# Regulation_Charging.net
KiCad netlist of a schematic drawn in Altium Designer
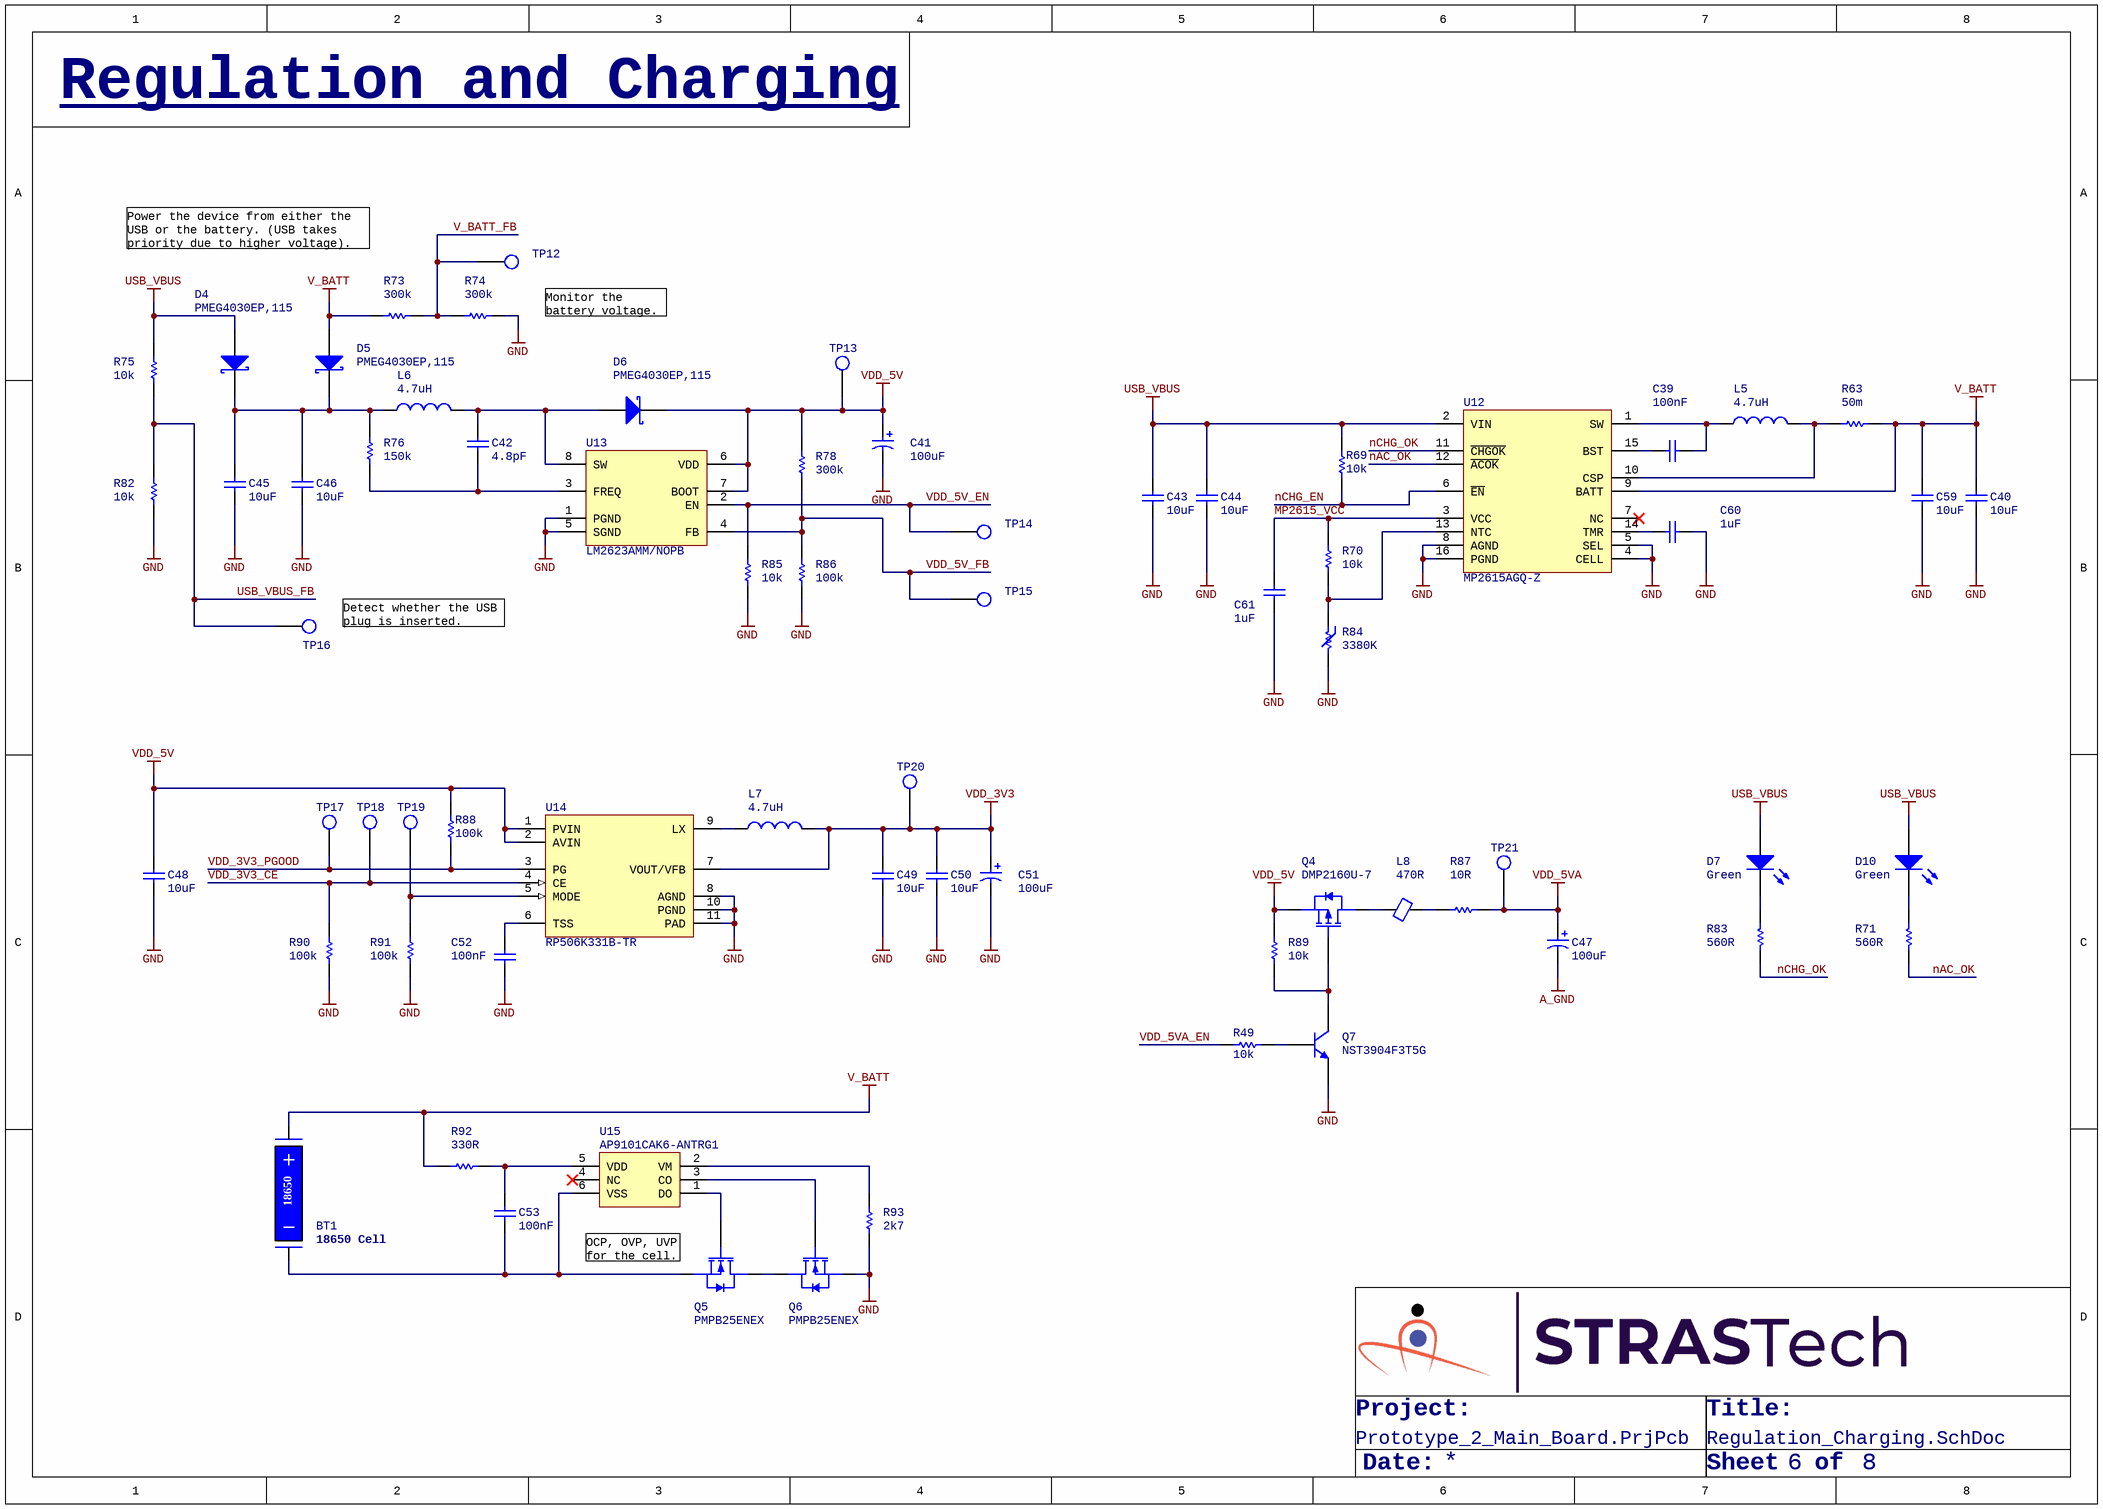
[diagram p0: Regulation_Charging.SchDoc]

(export (version "E")
  (design (tool "Eeschema 10.0.6"))
  (components
    (comp (ref "BT1")
      (value "Holder,Cell,18650,SMD")
      (footprint "HOLDER,CELL,18650,SMD")
      (description "Battery Holder (Open) 18650 1 Cell SMD (SMT) Tab")
      (fields
        (field (name "MANUFACTURER") "Keystone Electronics")
        (field (name "MANUFACTURER PART NUMBER") "1042")
        (field (name "CREATEDBY") "Judd Foster")
      )
      (libsource (lib "symbols") (part "Holder,Cell,18650,SMD"))
    )
    (comp (ref "C39")
      (value "100nF")
      (footprint "Cap,SMD,0402")
      (description "0.1µF ±10% 25V Ceramic Capacitor X7R 0402 (1005 Metric)")
      (fields
        (field (name "VENDOR PART NUMBER") "490-14603-1-ND")
        (field (name "MANUFACTURER") "Murata Electronics")
        (field (name "CREATEDBY") "Judd Foster")
      )
      (libsource (lib "symbols") (part "CAP,Cer,100nF,25VDC,X7R,0402"))
    )
    (comp (ref "C40")
      (value "10uF")
      (footprint "Cap,SMD,0402")
      (description "10 µF ±20% 10V Ceramic Capacitor X5R 0402 (1005 Metric)")
      (fields
        (field (name "VENDOR PART NUMBER") "1276-1450-1-ND")
        (field (name "MANUFACTURER") "Samsung Electro-Mechanics")
        (field (name "CREATEDBY") "Judd Foster")
      )
      (libsource (lib "symbols") (part "CAP,Cer,10uF,10VDC,X5R,0402"))
    )
    (comp (ref "C41")
      (value "100uF")
      (footprint "Cap,Alum,SMD,D5,H5.8")
      (description "CAP ALUM 100UF 20% 10V SMD")
      (fields
        (field (name "VENDOR PART NUMBER") "PCE3867CT-ND")
        (field (name "MANUFACTURER") "Panasonic")
        (field (name "CREATEDBY") "Judd Foster")
      )
      (libsource (lib "symbols") (part "CAP,Alum,100uF,10VDC,SMD"))
    )
    (comp (ref "C42")
      (value "4.8pF")
      (footprint "Cap,SMD,0402")
      (description "4.8 pF ±0.25pF 50V Ceramic Capacitor C0G, NP0 0402 (1005 Metric)")
      (fields
        (field (name "VENDOR PART NUMBER") "490-17481-1-ND")
        (field (name "MANUFACTURER") "Murata Electronics")
        (field (name "CREATEDBY") "Judd Foster")
      )
      (libsource (lib "symbols") (part "CAP,Cer,4.8pF,50VDC,C0G/NP0,0402"))
    )
    (comp (ref "C43")
      (value "10uF")
      (footprint "Cap,SMD,0402")
      (description "10 µF ±20% 10V Ceramic Capacitor X5R 0402 (1005 Metric)")
      (fields
        (field (name "VENDOR PART NUMBER") "1276-1450-1-ND")
        (field (name "MANUFACTURER") "Samsung Electro-Mechanics")
        (field (name "CREATEDBY") "Judd Foster")
      )
      (libsource (lib "symbols") (part "CAP,Cer,10uF,10VDC,X5R,0402"))
    )
    (comp (ref "C44")
      (value "10uF")
      (footprint "Cap,SMD,0402")
      (description "10 µF ±20% 10V Ceramic Capacitor X5R 0402 (1005 Metric)")
      (fields
        (field (name "VENDOR PART NUMBER") "1276-1450-1-ND")
        (field (name "MANUFACTURER") "Samsung Electro-Mechanics")
        (field (name "CREATEDBY") "Judd Foster")
      )
      (libsource (lib "symbols") (part "CAP,Cer,10uF,10VDC,X5R,0402"))
    )
    (comp (ref "C45")
      (value "10uF")
      (footprint "Cap,SMD,0402")
      (description "10 µF ±20% 10V Ceramic Capacitor X5R 0402 (1005 Metric)")
      (fields
        (field (name "VENDOR PART NUMBER") "1276-1450-1-ND")
        (field (name "MANUFACTURER") "Samsung Electro-Mechanics")
        (field (name "CREATEDBY") "Judd Foster")
      )
      (libsource (lib "symbols") (part "CAP,Cer,10uF,10VDC,X5R,0402"))
    )
    (comp (ref "C46")
      (value "10uF")
      (footprint "Cap,SMD,0402")
      (description "10 µF ±20% 10V Ceramic Capacitor X5R 0402 (1005 Metric)")
      (fields
        (field (name "VENDOR PART NUMBER") "1276-1450-1-ND")
        (field (name "MANUFACTURER") "Samsung Electro-Mechanics")
        (field (name "CREATEDBY") "Judd Foster")
      )
      (libsource (lib "symbols") (part "CAP,Cer,10uF,10VDC,X5R,0402"))
    )
    (comp (ref "C47")
      (value "100uF")
      (footprint "Cap,Alum,SMD,D5,H5.8")
      (description "CAP ALUM 100UF 20% 10V SMD")
      (fields
        (field (name "VENDOR PART NUMBER") "PCE3867CT-ND")
        (field (name "MANUFACTURER") "Panasonic")
        (field (name "CREATEDBY") "Judd Foster")
      )
      (libsource (lib "symbols") (part "CAP,Alum,100uF,10VDC,SMD"))
    )
    (comp (ref "C48")
      (value "10uF")
      (footprint "Cap,SMD,0402")
      (description "10 µF ±20% 10V Ceramic Capacitor X5R 0402 (1005 Metric)")
      (fields
        (field (name "VENDOR PART NUMBER") "1276-1450-1-ND")
        (field (name "MANUFACTURER") "Samsung Electro-Mechanics")
        (field (name "CREATEDBY") "Judd Foster")
      )
      (libsource (lib "symbols") (part "CAP,Cer,10uF,10VDC,X5R,0402"))
    )
    (comp (ref "C49")
      (value "10uF")
      (footprint "Cap,SMD,0402")
      (description "10 µF ±20% 10V Ceramic Capacitor X5R 0402 (1005 Metric)")
      (fields
        (field (name "VENDOR PART NUMBER") "1276-1450-1-ND")
        (field (name "MANUFACTURER") "Samsung Electro-Mechanics")
        (field (name "CREATEDBY") "Judd Foster")
      )
      (libsource (lib "symbols") (part "CAP,Cer,10uF,10VDC,X5R,0402"))
    )
    (comp (ref "C50")
      (value "10uF")
      (footprint "Cap,SMD,0402")
      (description "10 µF ±20% 10V Ceramic Capacitor X5R 0402 (1005 Metric)")
      (fields
        (field (name "VENDOR PART NUMBER") "1276-1450-1-ND")
        (field (name "MANUFACTURER") "Samsung Electro-Mechanics")
        (field (name "CREATEDBY") "Judd Foster")
      )
      (libsource (lib "symbols") (part "CAP,Cer,10uF,10VDC,X5R,0402"))
    )
    (comp (ref "C51")
      (value "100uF")
      (footprint "Cap,Alum,SMD,D5,H5.8")
      (description "CAP ALUM 100UF 20% 10V SMD")
      (fields
        (field (name "VENDOR PART NUMBER") "PCE3867CT-ND")
        (field (name "MANUFACTURER") "Panasonic")
        (field (name "CREATEDBY") "Judd Foster")
      )
      (libsource (lib "symbols") (part "CAP,Alum,100uF,10VDC,SMD"))
    )
    (comp (ref "C52")
      (value "100nF")
      (footprint "Cap,SMD,0402")
      (description "0.1µF ±10% 25V Ceramic Capacitor X7R 0402 (1005 Metric)")
      (fields
        (field (name "VENDOR PART NUMBER") "490-14603-1-ND")
        (field (name "MANUFACTURER") "Murata Electronics")
        (field (name "CREATEDBY") "Judd Foster")
      )
      (libsource (lib "symbols") (part "CAP,Cer,100nF,25VDC,X7R,0402"))
    )
    (comp (ref "C53")
      (value "100nF")
      (footprint "Cap,SMD,0402")
      (description "0.1µF ±10% 25V Ceramic Capacitor X7R 0402 (1005 Metric)")
      (fields
        (field (name "VENDOR PART NUMBER") "490-14603-1-ND")
        (field (name "MANUFACTURER") "Murata Electronics")
        (field (name "CREATEDBY") "Judd Foster")
      )
      (libsource (lib "symbols") (part "CAP,Cer,100nF,25VDC,X7R,0402"))
    )
    (comp (ref "C59")
      (value "10uF")
      (footprint "Cap,SMD,0402")
      (description "10 µF ±20% 10V Ceramic Capacitor X5R 0402 (1005 Metric)")
      (fields
        (field (name "VENDOR PART NUMBER") "1276-1450-1-ND")
        (field (name "MANUFACTURER") "Samsung Electro-Mechanics")
        (field (name "CREATEDBY") "Judd Foster")
      )
      (libsource (lib "symbols") (part "CAP,Cer,10uF,10VDC,X5R,0402"))
    )
    (comp (ref "C60")
      (value "1uF")
      (footprint "Cap,SMD,0402")
      (description "1 µF ±10% 35V Ceramic Capacitor X5R 0402 (1005 Metric)")
      (fields
        (field (name "VENDOR PART NUMBER") "445-9073-1-ND")
        (field (name "MANUFACTURER") "TDK Corporation")
        (field (name "CREATEDBY") "Judd Foster")
      )
      (libsource (lib "symbols") (part "CAP,Cer,1uF,35VDC,X5R,0402"))
    )
    (comp (ref "C61")
      (value "1uF")
      (footprint "Cap,SMD,0402")
      (description "1 µF ±10% 35V Ceramic Capacitor X5R 0402 (1005 Metric)")
      (fields
        (field (name "VENDOR PART NUMBER") "445-9073-1-ND")
        (field (name "MANUFACTURER") "TDK Corporation")
        (field (name "CREATEDBY") "Judd Foster")
      )
      (libsource (lib "symbols") (part "CAP,Cer,1uF,35VDC,X5R,0402"))
    )
    (comp (ref "D4")
      (value "PMEG4030EP,115")
      (footprint "SOD128")
      (description "Diode Schottky 40V 3A Surface Mount CFP5")
      (fields
        (field (name "MANUFACTURER") "Nexperia USA Inc.")
        (field (name "VENDOR PART NUMBER") "1727-5841-1-ND")
        (field (name "CREATEDBY") "Judd Foster")
      )
      (libsource (lib "symbols") (part "DIODE,Schottky,40V,3A,SMD"))
    )
    (comp (ref "D5")
      (value "PMEG4030EP,115")
      (footprint "SOD128")
      (description "Diode Schottky 40V 3A Surface Mount CFP5")
      (fields
        (field (name "MANUFACTURER") "Nexperia USA Inc.")
        (field (name "VENDOR PART NUMBER") "1727-5841-1-ND")
        (field (name "CREATEDBY") "Judd Foster")
      )
      (libsource (lib "symbols") (part "DIODE,Schottky,40V,3A,SMD"))
    )
    (comp (ref "D6")
      (value "PMEG4030EP,115")
      (footprint "SOD128")
      (description "Diode Schottky 40V 3A Surface Mount CFP5")
      (fields
        (field (name "MANUFACTURER") "Nexperia USA Inc.")
        (field (name "VENDOR PART NUMBER") "1727-5841-1-ND")
        (field (name "CREATEDBY") "Judd Foster")
      )
      (libsource (lib "symbols") (part "DIODE,Schottky,40V,3A,SMD"))
    )
    (comp (ref "D7")
      (value "Green")
      (footprint "LED,0603")
      (description "Green 530nm LED Indication - Discrete 3V 0603 (1608 Metric)")
      (fields
        (field (name "MANUFACTURER") "Stanley Electric Co")
        (field (name "MANUFACTURER PART NUMBER") "THG1111C-0005-TR")
        (field (name "CREATEDBY") "Judd Foster")
      )
      (libsource (lib "symbols") (part "LED,Green,SMD,0603"))
    )
    (comp (ref "D10")
      (value "Green")
      (footprint "LED,0603")
      (description "Green 530nm LED Indication - Discrete 3V 0603 (1608 Metric)")
      (fields
        (field (name "MANUFACTURER") "Stanley Electric Co")
        (field (name "MANUFACTURER PART NUMBER") "THG1111C-0005-TR")
        (field (name "CREATEDBY") "Judd Foster")
      )
      (libsource (lib "symbols") (part "LED,Green,SMD,0603"))
    )
    (comp (ref "L5")
      (value "4.7uH")
      (footprint "IND,WIREWOUND,4.9x4.9,SMD")
      (description "4.7µH Shielded Wirewound Inductor 2.6A 45.5mOhm Max Nonstandard")
      (fields
        (field (name "VENDOR PART NUMBER") "587-3605-1-ND")
        (field (name "MANUFACTURER") "Taiyo Yuden")
        (field (name "CREATEDBY") "Judd Foster")
      )
      (libsource (lib "symbols") (part "IND,4.7uH,2.6A,Wirewound,SMD"))
    )
    (comp (ref "L6")
      (value "4.7uH")
      (footprint "IND,WIREWOUND,4.9x4.9,SMD")
      (description "4.7µH Shielded Wirewound Inductor 2.6A 45.5mOhm Max Nonstandard")
      (fields
        (field (name "VENDOR PART NUMBER") "587-3605-1-ND")
        (field (name "MANUFACTURER") "Taiyo Yuden")
        (field (name "CREATEDBY") "Judd Foster")
      )
      (libsource (lib "symbols") (part "IND,4.7uH,2.6A,Wirewound,SMD"))
    )
    (comp (ref "L7")
      (value "4.7uH")
      (footprint "IND,WIREWOUND,4.9x4.9,SMD")
      (description "4.7µH Shielded Wirewound Inductor 2.6A 45.5mOhm Max Nonstandard")
      (fields
        (field (name "VENDOR PART NUMBER") "587-3605-1-ND")
        (field (name "MANUFACTURER") "Taiyo Yuden")
        (field (name "CREATEDBY") "Judd Foster")
      )
      (libsource (lib "symbols") (part "IND,4.7uH,2.6A,Wirewound,SMD"))
    )
    (comp (ref "L8")
      (value "470R")
      (footprint "IND,0402")
      (description "470 Ohms @ 100 MHz 1 Power Line Ferrite Bead 0402 (1005 Metric) 1A 200mOhm")
      (fields
        (field (name "VENDOR PART NUMBER") "490-10662-1-ND")
        (field (name "MANUFACTURER") "Murata Electronics")
        (field (name "CREATEDBY") "Judd Foster")
      )
      (libsource (lib "symbols") (part "Ferrite,470R@100MHz,0402"))
    )
    (comp (ref "Q4")
      (value "DMP2160U-7")
      (footprint "SOT23-3")
      (description "P-Channel 20 V 3.2A (Ta) 1.4W (Ta) Surface Mount SOT-23-3")
      (fields
        (field (name "MANUFACTURER") "Diodes Incorporated")
        (field (name "VENDOR PART NUMBER") "DMP2160UDICT-ND")
        (field (name "CREATEDBY") "Judd Foster")
      )
      (libsource (lib "symbols") (part "MOSFET,P Ch,20V,3.2A"))
    )
    (comp (ref "Q5")
      (value "PMPB25ENEX")
      (footprint "IC,WDFN-6,P0.65")
      (description "N-Channel 30 V 10A (Ta) 2.1W (Ta) Surface Mount DFN2020MD-6")
      (fields
        (field (name "MANUFACTURER") "Nexperia USA Inc.")
        (field (name "VENDOR PART NUMBER") "1727-7662-1-ND")
        (field (name "CREATEDBY") "Ritesh Nandakumar")
      )
      (libsource (lib "symbols") (part "MOSFET,N Ch,30V,10A"))
    )
    (comp (ref "Q6")
      (value "PMPB25ENEX")
      (footprint "IC,WDFN-6,P0.65")
      (description "N-Channel 30 V 10A (Ta) 2.1W (Ta) Surface Mount DFN2020MD-6")
      (fields
        (field (name "MANUFACTURER") "Nexperia USA Inc.")
        (field (name "VENDOR PART NUMBER") "1727-7662-1-ND")
        (field (name "CREATEDBY") "Ritesh Nandakumar")
      )
      (libsource (lib "symbols") (part "MOSFET,N Ch,30V,10A"))
    )
    (comp (ref "Q7")
      (value "NST3904F3T5G")
      (footprint "SOT1123")
      (description "Bipolar (BJT) Transistor NPN 40 V 200 mA 200MHz 290 mW Surface Mount SOT-1123")
      (fields
        (field (name "MANUFACTURER") "ON Semiconductor")
        (field (name "VENDOR PART NUMBER") "NST3904F3T5GOSCT-ND")
        (field (name "CREATEDBY") "Judd Foster")
      )
      (libsource (lib "symbols") (part "Trans,NPN,40V,200mA,SOT1123"))
    )
    (comp (ref "R49")
      (value "10k")
      (footprint "RES,0402")
      (description "10 kOhms ±5% 0.063W, 1/16W Chip Resistor 0402 (1005 Metric) Automotive AEC-Q200 Thick Film")
      (fields
        (field (name "VENDOR PART NUMBER") "RMCF0402JT10K0CT-ND")
        (field (name "MANUFACTURER") "Stackpole Electronics Inc")
        (field (name "CREATEDBY") "Judd Foster")
      )
      (libsource (lib "symbols") (part "RES,10k,5%,0.063W,0402"))
    )
    (comp (ref "R63")
      (value "50m")
      (footprint "RES,1206")
      (description "50 mOhms ±1% 0.5W, 1/2W Chip Resistor 1206 (3216 Metric) Current Sense Metal Film")
      (fields
        (field (name "MANUFACTURER") "Ohmite")
        (field (name "MANUFACTURER PART NUMBER") "KDV12FR050ET")
        (field (name "CREATEDBY") "Judd Foster")
      )
      (libsource (lib "symbols") (part "RES,50m,1%,0.5W,1206"))
    )
    (comp (ref "R69")
      (value "10k")
      (footprint "RES,0402")
      (description "10 kOhms ±5% 0.063W, 1/16W Chip Resistor 0402 (1005 Metric) Automotive AEC-Q200 Thick Film")
      (fields
        (field (name "VENDOR PART NUMBER") "RMCF0402JT10K0CT-ND")
        (field (name "MANUFACTURER") "Stackpole Electronics Inc")
        (field (name "CREATEDBY") "Judd Foster")
      )
      (libsource (lib "symbols") (part "RES,10k,5%,0.063W,0402"))
    )
    (comp (ref "R70")
      (value "10k")
      (footprint "RES,0402")
      (description "10 kOhms ±5% 0.063W, 1/16W Chip Resistor 0402 (1005 Metric) Automotive AEC-Q200 Thick Film")
      (fields
        (field (name "VENDOR PART NUMBER") "RMCF0402JT10K0CT-ND")
        (field (name "MANUFACTURER") "Stackpole Electronics Inc")
        (field (name "CREATEDBY") "Judd Foster")
      )
      (libsource (lib "symbols") (part "RES,10k,5%,0.063W,0402"))
    )
    (comp (ref "R71")
      (value "560R")
      (footprint "RES,0402")
      (fields
        (field (name "MANUFACTURER") "TE Connectivity Passive Product")
        (field (name "MANUFACTURER PART NUMBER") "CRGCQ0402F560R")
        (field (name "VENDOR PART NUMBER") "A129624CT-ND")
        (field (name "CREATEDBY") "Judd Foster")
      )
      (libsource (lib "symbols") (part "RES,560R,1%,0.063W,0402"))
    )
    (comp (ref "R73")
      (value "300k")
      (footprint "RES,0402")
      (description "300 kOhms ±1% 0.063W, 1/16W Chip Resistor 0402 (1005 Metric) Automotive AEC-Q200 Thick Film")
      (fields
        (field (name "MANUFACTURER") "Stackpole Electronics Inc")
        (field (name "MANUFACTURER PART NUMBER") "RMCF0402FT300K")
        (field (name "CREATEDBY") "Judd Foster")
      )
      (libsource (lib "symbols") (part "RES,300k,1%,0.063W,0402"))
    )
    (comp (ref "R74")
      (value "300k")
      (footprint "RES,0402")
      (description "300 kOhms ±1% 0.063W, 1/16W Chip Resistor 0402 (1005 Metric) Automotive AEC-Q200 Thick Film")
      (fields
        (field (name "MANUFACTURER") "Stackpole Electronics Inc")
        (field (name "MANUFACTURER PART NUMBER") "RMCF0402FT300K")
        (field (name "CREATEDBY") "Judd Foster")
      )
      (libsource (lib "symbols") (part "RES,300k,1%,0.063W,0402"))
    )
    (comp (ref "R75")
      (value "10k")
      (footprint "RES,0402")
      (description "10 kOhms ±5% 0.063W, 1/16W Chip Resistor 0402 (1005 Metric) Automotive AEC-Q200 Thick Film")
      (fields
        (field (name "VENDOR PART NUMBER") "RMCF0402JT10K0CT-ND")
        (field (name "MANUFACTURER") "Stackpole Electronics Inc")
        (field (name "CREATEDBY") "Judd Foster")
      )
      (libsource (lib "symbols") (part "RES,10k,5%,0.063W,0402"))
    )
    (comp (ref "R76")
      (value "150k")
      (footprint "RES,0402")
      (description "150 kOhms ±1% 0.063W, 1/16W Chip Resistor 0402 (1005 Metric) Automotive AEC-Q200 Thick Film")
      (fields
        (field (name "MANUFACTURER") "Stackpole Electronics Inc")
        (field (name "MANUFACTURER PART NUMBER") "RMCF0402FT150K")
        (field (name "CREATEDBY") "Judd Foster")
      )
      (libsource (lib "symbols") (part "RES,150k,1%,0.1W,0402"))
    )
    (comp (ref "R78")
      (value "300k")
      (footprint "RES,0402")
      (description "300 kOhms ±1% 0.063W, 1/16W Chip Resistor 0402 (1005 Metric) Automotive AEC-Q200 Thick Film")
      (fields
        (field (name "MANUFACTURER") "Stackpole Electronics Inc")
        (field (name "MANUFACTURER PART NUMBER") "RMCF0402FT300K")
        (field (name "CREATEDBY") "Judd Foster")
      )
      (libsource (lib "symbols") (part "RES,300k,1%,0.063W,0402"))
    )
    (comp (ref "R82")
      (value "10k")
      (footprint "RES,0402")
      (description "10 kOhms ±5% 0.063W, 1/16W Chip Resistor 0402 (1005 Metric) Automotive AEC-Q200 Thick Film")
      (fields
        (field (name "VENDOR PART NUMBER") "RMCF0402JT10K0CT-ND")
        (field (name "MANUFACTURER") "Stackpole Electronics Inc")
        (field (name "CREATEDBY") "Judd Foster")
      )
      (libsource (lib "symbols") (part "RES,10k,5%,0.063W,0402"))
    )
    (comp (ref "R83")
      (value "560R")
      (footprint "RES,0402")
      (fields
        (field (name "MANUFACTURER") "TE Connectivity Passive Product")
        (field (name "MANUFACTURER PART NUMBER") "CRGCQ0402F560R")
        (field (name "VENDOR PART NUMBER") "A129624CT-ND")
        (field (name "CREATEDBY") "Judd Foster")
      )
      (libsource (lib "symbols") (part "RES,560R,1%,0.063W,0402"))
    )
    (comp (ref "R84")
      (value "3380K")
      (footprint "RES,0402")
      (description "NTC Thermistor 10k 0402 (1005 Metric)")
      (fields
        (field (name "MANUFACTURER") "Murata Electronics")
        (field (name "MANUFACTURER PART NUMBER") "NCU15XH103J6SRC")
        (field (name "CREATEDBY") "Judd Foster")
      )
      (libsource (lib "symbols") (part "RES,Thermistor,3380K,0402"))
    )
    (comp (ref "R85")
      (value "10k")
      (footprint "RES,0402")
      (description "10 kOhms ±5% 0.063W, 1/16W Chip Resistor 0402 (1005 Metric) Automotive AEC-Q200 Thick Film")
      (fields
        (field (name "VENDOR PART NUMBER") "RMCF0402JT10K0CT-ND")
        (field (name "MANUFACTURER") "Stackpole Electronics Inc")
        (field (name "CREATEDBY") "Judd Foster")
      )
      (libsource (lib "symbols") (part "RES,10k,5%,0.063W,0402"))
    )
    (comp (ref "R86")
      (value "100k")
      (footprint "RES,0402")
      (description "100 kOhms ±5% 0.1W, 1/10W Chip Resistor 0402 (1005 Metric) Automotive AEC-Q200 Thick Film")
      (fields
        (field (name "MANUFACTURER") "Panasonic Electronic Components")
        (field (name "MANUFACTURER PART NUMBER") "ERJ-2GEJ104X")
        (field (name "CREATEDBY") "Judd Foster")
      )
      (libsource (lib "symbols") (part "RES,100k,5%,0.1W,0402"))
    )
    (comp (ref "R87")
      (value "10R")
      (footprint "RES,0402")
      (description "10 Ohms ±1% 0.063W, 1/16W Chip Resistor 0402 (1005 Metric) Automotive AEC-Q200 Thick Film")
      (fields
        (field (name "MANUFACTURER") "Panasonic Electronic Components")
        (field (name "MANUFACTURER PART NUMBER") "ERJ-2RKF10R0X")
        (field (name "CREATEDBY") "Judd Foster")
      )
      (libsource (lib "symbols") (part "RES,10R,1%,0.063W,0402"))
    )
    (comp (ref "R88")
      (value "100k")
      (footprint "RES,0402")
      (description "100 kOhms ±5% 0.1W, 1/10W Chip Resistor 0402 (1005 Metric) Automotive AEC-Q200 Thick Film")
      (fields
        (field (name "MANUFACTURER") "Panasonic Electronic Components")
        (field (name "MANUFACTURER PART NUMBER") "ERJ-2GEJ104X")
        (field (name "CREATEDBY") "Judd Foster")
      )
      (libsource (lib "symbols") (part "RES,100k,5%,0.1W,0402"))
    )
    (comp (ref "R89")
      (value "10k")
      (footprint "RES,0402")
      (description "10 kOhms ±5% 0.063W, 1/16W Chip Resistor 0402 (1005 Metric) Automotive AEC-Q200 Thick Film")
      (fields
        (field (name "VENDOR PART NUMBER") "RMCF0402JT10K0CT-ND")
        (field (name "MANUFACTURER") "Stackpole Electronics Inc")
        (field (name "CREATEDBY") "Judd Foster")
      )
      (libsource (lib "symbols") (part "RES,10k,5%,0.063W,0402"))
    )
    (comp (ref "R90")
      (value "100k")
      (footprint "RES,0402")
      (description "100 kOhms ±5% 0.1W, 1/10W Chip Resistor 0402 (1005 Metric) Automotive AEC-Q200 Thick Film")
      (fields
        (field (name "MANUFACTURER") "Panasonic Electronic Components")
        (field (name "MANUFACTURER PART NUMBER") "ERJ-2GEJ104X")
        (field (name "CREATEDBY") "Judd Foster")
      )
      (libsource (lib "symbols") (part "RES,100k,5%,0.1W,0402"))
    )
    (comp (ref "R91")
      (value "100k")
      (footprint "RES,0402")
      (description "100 kOhms ±5% 0.1W, 1/10W Chip Resistor 0402 (1005 Metric) Automotive AEC-Q200 Thick Film")
      (fields
        (field (name "MANUFACTURER") "Panasonic Electronic Components")
        (field (name "MANUFACTURER PART NUMBER") "ERJ-2GEJ104X")
        (field (name "CREATEDBY") "Judd Foster")
      )
      (libsource (lib "symbols") (part "RES,100k,5%,0.1W,0402"))
    )
    (comp (ref "R92")
      (value "330R")
      (footprint "RES,0402")
      (description "330 Ohms ±5% 0.063W, 1/16W Chip Resistor 0402 (1005 Metric) Automotive AEC-Q200 Thick Film")
      (fields
        (field (name "MANUFACTURER") "Stackpole Electronics Inc")
        (field (name "MANUFACTURER PART NUMBER") "RMCF0402JT330R")
        (field (name "CREATEDBY") "Judd Foster")
      )
      (libsource (lib "symbols") (part "RES,330R,5%,0.063W,0402"))
    )
    (comp (ref "R93")
      (value "2k7")
      (footprint "RES,0402")
      (description "2.7 kOhms ±1% 0.063W, 1/16W Chip Resistor 0402 (1005 Metric) Automotive AEC-Q200 Thick Film")
      (fields
        (field (name "MANUFACTURER") "Stackpole Electronics Inc")
        (field (name "MANUFACTURER PART NUMBER") "RMCF0402FT2K70")
        (field (name "CREATEDBY") "Judd Foster")
      )
      (libsource (lib "symbols") (part "RES,2k7,1%,0.063W,0402"))
    )
    (comp (ref "TP12")
      (value "TESTPOINT")
      (footprint "testpoint,smd,round,1mm")
      (description "PCB Testpoint")
      (fields (field (name "CREATEDBY") "Judd Foster"))
      (libsource (lib "symbols") (part "TESTPOINT"))
    )
    (comp (ref "TP13")
      (value "TESTPOINT")
      (footprint "testpoint,smd,round,1mm")
      (description "PCB Testpoint")
      (fields (field (name "CREATEDBY") "Judd Foster"))
      (libsource (lib "symbols") (part "TESTPOINT"))
    )
    (comp (ref "TP14")
      (value "TESTPOINT")
      (footprint "testpoint,smd,round,1mm")
      (description "PCB Testpoint")
      (fields (field (name "CREATEDBY") "Judd Foster"))
      (libsource (lib "symbols") (part "TESTPOINT"))
    )
    (comp (ref "TP15")
      (value "TESTPOINT")
      (footprint "testpoint,smd,round,1mm")
      (description "PCB Testpoint")
      (fields (field (name "CREATEDBY") "Judd Foster"))
      (libsource (lib "symbols") (part "TESTPOINT"))
    )
    (comp (ref "TP16")
      (value "TESTPOINT")
      (footprint "testpoint,smd,round,1mm")
      (description "PCB Testpoint")
      (fields (field (name "CREATEDBY") "Judd Foster"))
      (libsource (lib "symbols") (part "TESTPOINT"))
    )
    (comp (ref "TP17")
      (value "TESTPOINT")
      (footprint "testpoint,smd,round,1mm")
      (description "PCB Testpoint")
      (fields (field (name "CREATEDBY") "Judd Foster"))
      (libsource (lib "symbols") (part "TESTPOINT"))
    )
    (comp (ref "TP18")
      (value "TESTPOINT")
      (footprint "testpoint,smd,round,1mm")
      (description "PCB Testpoint")
      (fields (field (name "CREATEDBY") "Judd Foster"))
      (libsource (lib "symbols") (part "TESTPOINT"))
    )
    (comp (ref "TP19")
      (value "TESTPOINT")
      (footprint "testpoint,smd,round,1mm")
      (description "PCB Testpoint")
      (fields (field (name "CREATEDBY") "Judd Foster"))
      (libsource (lib "symbols") (part "TESTPOINT"))
    )
    (comp (ref "TP20")
      (value "TESTPOINT")
      (footprint "testpoint,smd,round,1mm")
      (description "PCB Testpoint")
      (fields (field (name "CREATEDBY") "Judd Foster"))
      (libsource (lib "symbols") (part "TESTPOINT"))
    )
    (comp (ref "TP21")
      (value "TESTPOINT")
      (footprint "testpoint,smd,round,1mm")
      (description "PCB Testpoint")
      (fields (field (name "CREATEDBY") "Judd Foster"))
      (libsource (lib "symbols") (part "TESTPOINT"))
    )
    (comp (ref "U12")
      (value "MP2615AGQ-Z")
      (footprint "IC,QFN-16,3x3,P5x3")
      (description "Charger IC Lithium Ion/Polymer 16-QFN (3x3)")
      (fields
        (field (name "MANUFACTURER") "Monolithic Power Systems Inc.")
        (field (name "VENDOR PART NUMBER") "1589-MP2615AGQ-ZCT-ND")
        (field (name "CREATEDBY") "Judd Foster")
      )
      (libsource (lib "symbols") (part "MP2615AGQ-Z"))
    )
    (comp (ref "U13")
      (value "LM2623AMM/NOPB")
      (footprint "IC,TSSOP-8,W3.0")
      (fields
        (field (name "VENDOR PART NUMBER") "LM2623AMM/NOPBCT-ND")
        (field (name "MANUFACTURER") "Texas Instruments")
        (field (name "CREATEDBY") "Judd Foster")
      )
      (libsource (lib "symbols") (part "LM2623AMM/NOPB"))
    )
    (comp (ref "U14")
      (value "RP506K331B-TR")
      (footprint "IC,DFN-10_3x3,P0.5mm")
      (description "Buck Switching Regulator IC Positive Fixed 3.3V 1 Output 2A 10-UFDFN Exposed Pad")
      (fields
        (field (name "MANUFACTURER") "Nisshinbo Micro Devices Inc.")
        (field (name "VENDOR PART NUMBER") "2129-RP506K331B-CT-ND")
        (field (name "CREATEDBY") "Judd Foster")
      )
      (libsource (lib "symbols") (part "RP506K331B-TR"))
    )
    (comp (ref "U15")
      (value "AP9101CAK6-ANTRG1")
      (footprint "SOT23-6")
      (description "Battery Battery Protection IC Lithium Ion/Polymer SOT-26")
      (fields
        (field (name "MANUFACTURER") "Diodes Incorporated")
        (field (name "VENDOR PART NUMBER") "AP9101CAK6-ANTRG1DICT-ND")
        (field (name "CREATEDBY") "Judd Foster")
      )
      (libsource (lib "symbols") (part "AP9101CAK6-ANTRG1"))
    )
  )
  (nets
    (net (code "1") (name "/MP2615_VCC") (class "Default")
      (node (ref "C61") (pin "2") (pinfunction "2_2") (pintype "passive"))
      (node (ref "R70") (pin "1") (pinfunction "1_1") (pintype "passive"))
      (node (ref "U12") (pin "3") (pinfunction "VCC_3") (pintype "passive"))
    )
    (net (code "2") (name "/USB_VBUS_FB") (class "Default")
      (node (ref "R75") (pin "1") (pinfunction "1_1") (pintype "passive"))
      (node (ref "R82") (pin "2") (pinfunction "2_2") (pintype "passive"))
      (node (ref "TP16") (pin "1") (pinfunction "TP_1") (pintype "passive"))
    )
    (net (code "3") (name "/VDD_3V3_CE") (class "Default")
      (node (ref "R90") (pin "2") (pinfunction "2_2") (pintype "passive"))
      (node (ref "TP18") (pin "1") (pinfunction "TP_1") (pintype "passive"))
      (node (ref "U14") (pin "4") (pinfunction "CE_4") (pintype "input"))
    )
    (net (code "4") (name "/VDD_3V3_PGOOD") (class "Default")
      (node (ref "R88") (pin "1") (pinfunction "1_1") (pintype "passive"))
      (node (ref "TP17") (pin "1") (pinfunction "TP_1") (pintype "passive"))
      (node (ref "U14") (pin "3") (pinfunction "PG_3") (pintype "open_collector"))
    )
    (net (code "5") (name "/VDD_5VA_EN") (class "Default")
      (node (ref "R49") (pin "2") (pinfunction "2_2") (pintype "passive"))
    )
    (net (code "6") (name "/VDD_5V_EN") (class "Default")
      (node (ref "R85") (pin "2") (pinfunction "2_2") (pintype "passive"))
      (node (ref "TP14") (pin "1") (pinfunction "TP_1") (pintype "passive"))
      (node (ref "U13") (pin "2") (pinfunction "EN_2") (pintype "passive"))
    )
    (net (code "7") (name "/VDD_5V_FB") (class "Default")
      (node (ref "R78") (pin "1") (pinfunction "1_1") (pintype "passive"))
      (node (ref "R86") (pin "2") (pinfunction "2_2") (pintype "passive"))
      (node (ref "TP15") (pin "1") (pinfunction "TP_1") (pintype "passive"))
      (node (ref "U13") (pin "4") (pinfunction "FB_4") (pintype "passive"))
    )
    (net (code "8") (name "/V_BATT_FB") (class "Default")
      (node (ref "R73") (pin "1") (pinfunction "1_1") (pintype "passive"))
      (node (ref "R74") (pin "2") (pinfunction "2_2") (pintype "passive"))
      (node (ref "TP12") (pin "1") (pinfunction "TP_1") (pintype "passive"))
    )
    (net (code "9") (name "/nAC_OK") (class "Default")
      (node (ref "R71") (pin "2") (pinfunction "2_2") (pintype "passive"))
      (node (ref "U12") (pin "12") (pinfunction "~{ACOK}_12") (pintype "passive"))
    )
    (net (code "10") (name "/nCHG_EN") (class "Default")
      (node (ref "R69") (pin "2") (pinfunction "2_2") (pintype "passive"))
      (node (ref "U12") (pin "6") (pinfunction "~{EN}_6") (pintype "passive"))
    )
    (net (code "11") (name "/nCHG_OK") (class "Default")
      (node (ref "R83") (pin "2") (pinfunction "2_2") (pintype "passive"))
      (node (ref "U12") (pin "11") (pinfunction "~{CHGOK}_11") (pintype "passive"))
    )
    (net (code "12") (name "A_GND") (class "Default")
      (node (ref "C47") (pin "2") (pinfunction "2_2") (pintype "passive"))
    )
    (net (code "13") (name "GND") (class "Default")
      (node (ref "C40") (pin "1") (pinfunction "1_1") (pintype "passive"))
      (node (ref "C41") (pin "2") (pinfunction "2_2") (pintype "passive"))
      (node (ref "C43") (pin "1") (pinfunction "1_1") (pintype "passive"))
      (node (ref "C44") (pin "1") (pinfunction "1_1") (pintype "passive"))
      (node (ref "C45") (pin "1") (pinfunction "1_1") (pintype "passive"))
      (node (ref "C46") (pin "1") (pinfunction "1_1") (pintype "passive"))
      (node (ref "C48") (pin "1") (pinfunction "1_1") (pintype "passive"))
      (node (ref "C49") (pin "1") (pinfunction "1_1") (pintype "passive"))
      (node (ref "C50") (pin "1") (pinfunction "1_1") (pintype "passive"))
      (node (ref "C51") (pin "2") (pinfunction "2_2") (pintype "passive"))
      (node (ref "C52") (pin "1") (pinfunction "1_1") (pintype "passive"))
      (node (ref "C59") (pin "1") (pinfunction "1_1") (pintype "passive"))
      (node (ref "C60") (pin "2") (pinfunction "2_2") (pintype "passive"))
      (node (ref "C61") (pin "1") (pinfunction "1_1") (pintype "passive"))
      (node (ref "Q6") (pin "3") (pinfunction "S_3") (pintype "passive"))
      (node (ref "Q7") (pin "2") (pinfunction "E_2") (pintype "passive"))
      (node (ref "R74") (pin "1") (pinfunction "1_1") (pintype "passive"))
      (node (ref "R82") (pin "1") (pinfunction "1_1") (pintype "passive"))
      (node (ref "R84") (pin "2") (pinfunction "2_2") (pintype "passive"))
      (node (ref "R85") (pin "1") (pinfunction "1_1") (pintype "passive"))
      (node (ref "R86") (pin "1") (pinfunction "1_1") (pintype "passive"))
      (node (ref "R90") (pin "1") (pinfunction "1_1") (pintype "passive"))
      (node (ref "R91") (pin "2") (pinfunction "2_2") (pintype "passive"))
      (node (ref "R93") (pin "1") (pinfunction "1_1") (pintype "passive"))
      (node (ref "U12") (pin "16") (pinfunction "PGND_16") (pintype "passive"))
      (node (ref "U12") (pin "4") (pinfunction "CELL_4") (pintype "passive"))
      (node (ref "U12") (pin "5") (pinfunction "SEL_5") (pintype "passive"))
      (node (ref "U12") (pin "8") (pinfunction "AGND_8") (pintype "passive"))
      (node (ref "U13") (pin "1") (pinfunction "PGND_1") (pintype "passive"))
      (node (ref "U13") (pin "5") (pinfunction "SGND_5") (pintype "passive"))
      (node (ref "U14") (pin "10") (pinfunction "PGND_10") (pintype "power_in"))
      (node (ref "U14") (pin "11") (pinfunction "PAD_11") (pintype "power_in"))
      (node (ref "U14") (pin "8") (pinfunction "AGND_8") (pintype "power_in"))
    )
    (net (code "14") (name "Net-(D4-K)") (class "Default")
      (node (ref "C45") (pin "2") (pinfunction "2_2") (pintype "passive"))
      (node (ref "C46") (pin "2") (pinfunction "2_2") (pintype "passive"))
      (node (ref "D4") (pin "1") (pinfunction "K_1") (pintype "passive"))
      (node (ref "D5") (pin "1") (pinfunction "K_1") (pintype "passive"))
      (node (ref "L6") (pin "1") (pinfunction "1_1") (pintype "passive"))
      (node (ref "R76") (pin "2") (pinfunction "2_2") (pintype "passive"))
    )
    (net (code "15") (name "Net-(D6-A)") (class "Default")
      (node (ref "C42") (pin "2") (pinfunction "2_2") (pintype "passive"))
      (node (ref "D6") (pin "2") (pinfunction "A_2") (pintype "passive"))
      (node (ref "L6") (pin "2") (pinfunction "2_2") (pintype "passive"))
      (node (ref "U13") (pin "8") (pinfunction "SW_8") (pintype "passive"))
    )
    (net (code "16") (name "Net-(D7-K)") (class "Default")
      (node (ref "D7") (pin "2") (pinfunction "K_2") (pintype "passive"))
      (node (ref "R83") (pin "1") (pinfunction "1_1") (pintype "passive"))
    )
    (net (code "17") (name "Net-(D10-K)") (class "Default")
      (node (ref "D10") (pin "2") (pinfunction "K_2") (pintype "passive"))
      (node (ref "R71") (pin "1") (pinfunction "1_1") (pintype "passive"))
    )
    (net (code "18") (name "Net-(L8-Pad2)") (class "Default")
      (node (ref "L8") (pin "2") (pinfunction "2_2") (pintype "passive"))
      (node (ref "R87") (pin "1") (pinfunction "1_1") (pintype "passive"))
    )
    (net (code "19") (name "Net-(Q4-D)") (class "Default")
      (node (ref "L8") (pin "1") (pinfunction "1_1") (pintype "passive"))
      (node (ref "Q4") (pin "3") (pinfunction "D_3") (pintype "passive"))
    )
    (net (code "20") (name "Net-(Q4-G)") (class "Default")
      (node (ref "Q4") (pin "1") (pinfunction "G_1") (pintype "passive"))
      (node (ref "Q7") (pin "3") (pinfunction "C_3") (pintype "passive"))
      (node (ref "R89") (pin "1") (pinfunction "1_1") (pintype "passive"))
    )
    (net (code "21") (name "Net-(Q5-D)") (class "Default")
      (node (ref "Q5") (pin "1") (pinfunction "D_1") (pintype "passive"))
      (node (ref "Q6") (pin "1") (pinfunction "D_1") (pintype "passive"))
    )
    (net (code "22") (name "Net-(Q5-G)") (class "Default")
      (node (ref "Q5") (pin "2") (pinfunction "G_2") (pintype "passive"))
      (node (ref "U15") (pin "1") (pinfunction "DO_1") (pintype "passive"))
    )
    (net (code "23") (name "Net-(Q5-S)") (class "Default")
      (node (ref "BT1") (pin "2") (pinfunction "2_2") (pintype "passive"))
      (node (ref "C53") (pin "1") (pinfunction "1_1") (pintype "passive"))
      (node (ref "Q5") (pin "3") (pinfunction "S_3") (pintype "passive"))
      (node (ref "U15") (pin "6") (pinfunction "VSS_6") (pintype "passive"))
    )
    (net (code "24") (name "Net-(Q6-G)") (class "Default")
      (node (ref "Q6") (pin "2") (pinfunction "G_2") (pintype "passive"))
      (node (ref "U15") (pin "3") (pinfunction "CO_3") (pintype "passive"))
    )
    (net (code "25") (name "Net-(Q7-B)") (class "Default")
      (node (ref "Q7") (pin "1") (pinfunction "B_1") (pintype "passive"))
      (node (ref "R49") (pin "1") (pinfunction "1_1") (pintype "passive"))
    )
    (net (code "26") (name "Net-(TP19-TP)") (class "Default")
      (node (ref "R91") (pin "1") (pinfunction "1_1") (pintype "passive"))
      (node (ref "TP19") (pin "1") (pinfunction "TP_1") (pintype "passive"))
      (node (ref "U14") (pin "5") (pinfunction "MODE_5") (pintype "input"))
    )
    (net (code "27") (name "Net-(U12-BST)") (class "Default")
      (node (ref "C39") (pin "2") (pinfunction "2_2") (pintype "passive"))
      (node (ref "U12") (pin "15") (pinfunction "BST_15") (pintype "passive"))
    )
    (net (code "28") (name "Net-(U12-CSP)") (class "Default")
      (node (ref "L5") (pin "2") (pinfunction "2_2") (pintype "passive"))
      (node (ref "R63") (pin "1") (pinfunction "1_1") (pintype "passive"))
      (node (ref "U12") (pin "10") (pinfunction "CSP_10") (pintype "passive"))
    )
    (net (code "29") (name "Net-(U12-NTC)") (class "Default")
      (node (ref "R70") (pin "2") (pinfunction "2_2") (pintype "passive"))
      (node (ref "R84") (pin "1") (pinfunction "1_1") (pintype "passive"))
      (node (ref "U12") (pin "13") (pinfunction "NTC_13") (pintype "passive"))
    )
    (net (code "30") (name "Net-(U12-SW)") (class "Default")
      (node (ref "C39") (pin "1") (pinfunction "1_1") (pintype "passive"))
      (node (ref "L5") (pin "1") (pinfunction "1_1") (pintype "passive"))
      (node (ref "U12") (pin "1") (pinfunction "SW_1") (pintype "passive"))
    )
    (net (code "31") (name "Net-(U12-TMR)") (class "Default")
      (node (ref "C60") (pin "1") (pinfunction "1_1") (pintype "passive"))
      (node (ref "U12") (pin "14") (pinfunction "TMR_14") (pintype "passive"))
    )
    (net (code "32") (name "Net-(U13-FREQ)") (class "Default")
      (node (ref "C42") (pin "1") (pinfunction "1_1") (pintype "passive"))
      (node (ref "R76") (pin "1") (pinfunction "1_1") (pintype "passive"))
      (node (ref "U13") (pin "3") (pinfunction "FREQ_3") (pintype "passive"))
    )
    (net (code "33") (name "Net-(U14-LX)") (class "Default")
      (node (ref "L7") (pin "1") (pinfunction "1_1") (pintype "passive"))
      (node (ref "U14") (pin "9") (pinfunction "LX_9") (pintype "passive"))
    )
    (net (code "34") (name "Net-(U14-TSS)") (class "Default")
      (node (ref "C52") (pin "2") (pinfunction "2_2") (pintype "passive"))
      (node (ref "U14") (pin "6") (pinfunction "TSS_6") (pintype "open_collector"))
    )
    (net (code "35") (name "Net-(U15-VDD)") (class "Default")
      (node (ref "C53") (pin "2") (pinfunction "2_2") (pintype "passive"))
      (node (ref "R92") (pin "2") (pinfunction "2_2") (pintype "passive"))
      (node (ref "U15") (pin "5") (pinfunction "VDD_5") (pintype "passive"))
    )
    (net (code "36") (name "Net-(U15-VM)") (class "Default")
      (node (ref "R93") (pin "2") (pinfunction "2_2") (pintype "passive"))
      (node (ref "U15") (pin "2") (pinfunction "VM_2") (pintype "passive"))
    )
    (net (code "37") (name "USB_VBUS") (class "Default")
      (node (ref "C43") (pin "2") (pinfunction "2_2") (pintype "passive"))
      (node (ref "C44") (pin "2") (pinfunction "2_2") (pintype "passive"))
      (node (ref "D10") (pin "1") (pinfunction "A_1") (pintype "passive"))
      (node (ref "D4") (pin "2") (pinfunction "A_2") (pintype "passive"))
      (node (ref "D7") (pin "1") (pinfunction "A_1") (pintype "passive"))
      (node (ref "R69") (pin "1") (pinfunction "1_1") (pintype "passive"))
      (node (ref "R75") (pin "2") (pinfunction "2_2") (pintype "passive"))
      (node (ref "U12") (pin "2") (pinfunction "VIN_2") (pintype "passive"))
    )
    (net (code "38") (name "VDD_3V3") (class "Default")
      (node (ref "C49") (pin "2") (pinfunction "2_2") (pintype "passive"))
      (node (ref "C50") (pin "2") (pinfunction "2_2") (pintype "passive"))
      (node (ref "C51") (pin "1") (pinfunction "1_1") (pintype "passive"))
      (node (ref "L7") (pin "2") (pinfunction "2_2") (pintype "passive"))
      (node (ref "TP20") (pin "1") (pinfunction "TP_1") (pintype "passive"))
      (node (ref "U14") (pin "7") (pinfunction "VOUT/VFB_7") (pintype "power_in"))
    )
    (net (code "39") (name "VDD_5V") (class "Default")
      (node (ref "C41") (pin "1") (pinfunction "1_1") (pintype "passive"))
      (node (ref "C48") (pin "2") (pinfunction "2_2") (pintype "passive"))
      (node (ref "D6") (pin "1") (pinfunction "K_1") (pintype "passive"))
      (node (ref "Q4") (pin "2") (pinfunction "S_2") (pintype "passive"))
      (node (ref "R78") (pin "2") (pinfunction "2_2") (pintype "passive"))
      (node (ref "R88") (pin "2") (pinfunction "2_2") (pintype "passive"))
      (node (ref "R89") (pin "2") (pinfunction "2_2") (pintype "passive"))
      (node (ref "TP13") (pin "1") (pinfunction "TP_1") (pintype "passive"))
      (node (ref "U13") (pin "6") (pinfunction "VDD_6") (pintype "passive"))
      (node (ref "U13") (pin "7") (pinfunction "BOOT_7") (pintype "passive"))
      (node (ref "U14") (pin "1") (pinfunction "PVIN_1") (pintype "power_in"))
      (node (ref "U14") (pin "2") (pinfunction "AVIN_2") (pintype "power_in"))
    )
    (net (code "40") (name "VDD_5VA") (class "Default")
      (node (ref "C47") (pin "1") (pinfunction "1_1") (pintype "passive"))
      (node (ref "R87") (pin "2") (pinfunction "2_2") (pintype "passive"))
      (node (ref "TP21") (pin "1") (pinfunction "TP_1") (pintype "passive"))
    )
    (net (code "41") (name "V_BATT") (class "Default")
      (node (ref "BT1") (pin "1") (pinfunction "1_1") (pintype "passive"))
      (node (ref "C40") (pin "2") (pinfunction "2_2") (pintype "passive"))
      (node (ref "C59") (pin "2") (pinfunction "2_2") (pintype "passive"))
      (node (ref "D5") (pin "2") (pinfunction "A_2") (pintype "passive"))
      (node (ref "R63") (pin "2") (pinfunction "2_2") (pintype "passive"))
      (node (ref "R73") (pin "2") (pinfunction "2_2") (pintype "passive"))
      (node (ref "R92") (pin "1") (pinfunction "1_1") (pintype "passive"))
      (node (ref "U12") (pin "9") (pinfunction "BATT_9") (pintype "passive"))
    )
    (net (code "42") (name "unconnected-(U12-NC-Pad7)") (class "Default")
      (node (ref "U12") (pin "7") (pinfunction "NC_7") (pintype "passive+no_connect"))
    )
    (net (code "43") (name "unconnected-(U15-NC-Pad4)") (class "Default")
      (node (ref "U15") (pin "4") (pinfunction "NC_4") (pintype "passive+no_connect"))
    )
  )
)
